# COMS0004_2_TXDevMux.net
KiCad netlist of a schematic drawn in Altium Designer
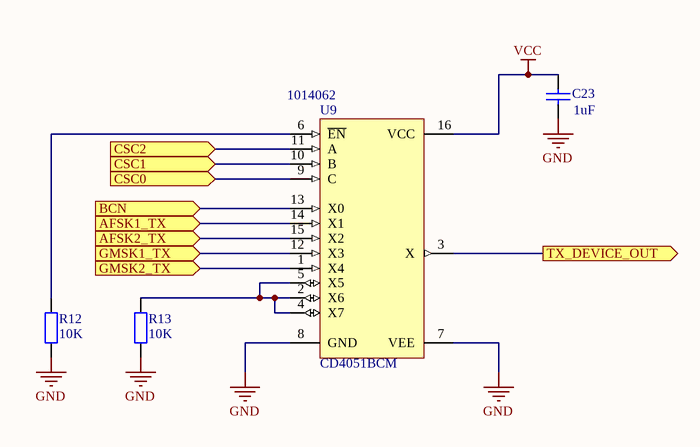
[diagram p0: COMS0004_2_TXDevMux.SchDoc]

(export (version "E")
  (design (tool "Eeschema 10.0.6"))
  (components
    (comp (ref "C23")
      (value "1uF")
      (footprint "0805")
      (description "Capacitor")
      (fields (field (name "Comment") "C1210") (field (name "PUBLISHER") "Altium Limited"))
      (libsource (lib "Miscellaneous Devices") (part "Cap"))
    )
    (comp (ref "R12")
      (value "10K")
      (footprint "RESC2012N")
      (description "Resistor")
      (fields (field (name "Comment") "Res1") (field (name "PUBLISHER") "Altium Limited"))
      (libsource (lib "Miscellaneous Devices") (part "Res2"))
    )
    (comp (ref "R13")
      (value "10K")
      (footprint "RESC2012N")
      (description "Resistor")
      (fields (field (name "Comment") "Res1") (field (name "PUBLISHER") "Altium Limited"))
      (libsource (lib "Miscellaneous Devices") (part "Res2"))
    )
    (comp (ref "U9")
      (value "CD4051BCM")
      (footprint "M16A_M")
      (description "8-Channel Analog Multiplexer/Demultiplexer")
      (fields (field (name "SUPPLIER PART NUMBER 1") "1014062") (field (name "PUBLISHER") "Altium Limited"))
      (libsource (lib "FSC Logic Multiplexer") (part "CD4051BCM"))
    )
  )
  (nets
    (net (code "1") (name "/AFSK1_TX") (class "Default")
      (node (ref "U9") (pin "14") (pinfunction "X1_14") (pintype "input"))
    )
    (net (code "2") (name "/AFSK2_TX") (class "Default")
      (node (ref "U9") (pin "15") (pinfunction "X2_15") (pintype "input"))
    )
    (net (code "3") (name "/BCN") (class "Default")
      (node (ref "U9") (pin "13") (pinfunction "X0_13") (pintype "input"))
    )
    (net (code "4") (name "/CSC0") (class "Default")
      (node (ref "U9") (pin "9") (pinfunction "C_9") (pintype "input"))
    )
    (net (code "5") (name "/CSC1") (class "Default")
      (node (ref "U9") (pin "10") (pinfunction "B_10") (pintype "input"))
    )
    (net (code "6") (name "/CSC2") (class "Default")
      (node (ref "U9") (pin "11") (pinfunction "A_11") (pintype "input"))
    )
    (net (code "7") (name "/GMSK1_TX") (class "Default")
      (node (ref "U9") (pin "12") (pinfunction "X3_12") (pintype "input"))
    )
    (net (code "8") (name "/GMSK2_TX") (class "Default")
      (node (ref "U9") (pin "1") (pinfunction "X4_1") (pintype "input"))
    )
    (net (code "9") (name "/TX_DEVICE_OUT") (class "Default")
      (node (ref "U9") (pin "3") (pinfunction "X_3") (pintype "output"))
    )
    (net (code "10") (name "GND") (class "Default")
      (node (ref "C23") (pin "1") (pinfunction "1_1") (pintype "passive"))
      (node (ref "R12") (pin "1") (pinfunction "1_1") (pintype "passive"))
      (node (ref "R13") (pin "1") (pinfunction "1_1") (pintype "passive"))
      (node (ref "U9") (pin "7") (pinfunction "VEE_7") (pintype "power_in"))
      (node (ref "U9") (pin "8") (pinfunction "GND_8") (pintype "power_in"))
    )
    (net (code "11") (name "Net-(U9-X5)") (class "Default")
      (node (ref "R13") (pin "2") (pinfunction "2_2") (pintype "passive"))
      (node (ref "U9") (pin "2") (pinfunction "X6_2") (pintype "bidirectional"))
      (node (ref "U9") (pin "4") (pinfunction "X7_4") (pintype "bidirectional"))
      (node (ref "U9") (pin "5") (pinfunction "X5_5") (pintype "bidirectional"))
    )
    (net (code "12") (name "Net-(U9-~{EN})") (class "Default")
      (node (ref "R12") (pin "2") (pinfunction "2_2") (pintype "passive"))
      (node (ref "U9") (pin "6") (pinfunction "~{EN}_6") (pintype "input"))
    )
    (net (code "13") (name "VCC") (class "Default")
      (node (ref "C23") (pin "2") (pinfunction "2_2") (pintype "passive"))
      (node (ref "U9") (pin "16") (pinfunction "VCC_16") (pintype "power_in"))
    )
  )
)
